# zxld400-9-leds-mk-2-driver.net
KiCad netlist of a schematic drawn in EAGLE
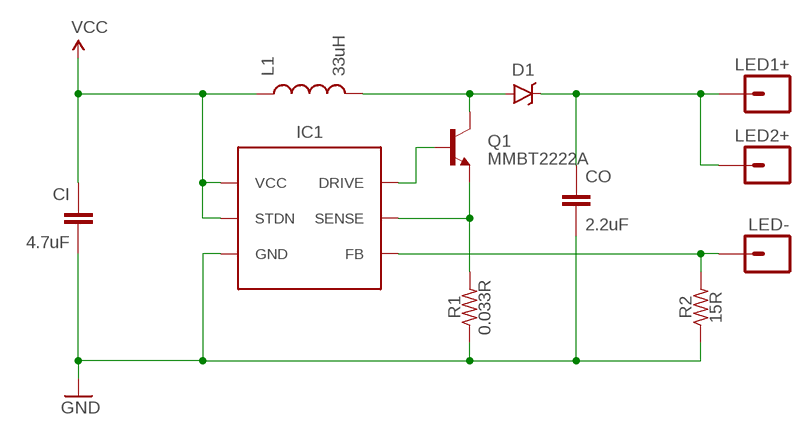
[diagram p0: schematic, sheet 1]

(export (version "E")
  (design (tool "Eeschema 10.0.6"))
  (components
    (comp (ref "CI")
      (value "4.7uF")
      (footprint "eagle-import:C0805")
      (libsource (lib "eagle-import") (part "CAPACITOR-CERAMICC0805"))
    )
    (comp (ref "CO")
      (value "2.2uF")
      (footprint "eagle-import:C0805")
      (libsource (lib "eagle-import") (part "CAPACITOR-CERAMICC0805"))
    )
    (comp (ref "D1")
      (value "DIODE-SCHOTTKYSMA")
      (footprint "eagle-import:SMA-DIODE-SCHOTTKY")
      (libsource (lib "eagle-import") (part "DIODE-SCHOTTKYSMA"))
    )
    (comp (ref "IC1")
      (value "ZXSC400")
      (footprint "eagle-import:SOT23-6")
      (libsource (lib "eagle-import") (part "ZXSC400"))
    )
    (comp (ref "L1")
      (value "33uH")
      (footprint "eagle-import:TAIYO-YUDEN-30XX")
      (libsource (lib "eagle-import") (part "INDUCTORTAIYO-YUDEN-30XX"))
    )
    (comp (ref "LED-")
      (value "M01PTH")
      (footprint "eagle-import:1X01")
      (libsource (lib "eagle-import") (part "M01PTH"))
    )
    (comp (ref "LED1+")
      (value "M01PTH")
      (footprint "eagle-import:1X01")
      (libsource (lib "eagle-import") (part "M01PTH"))
    )
    (comp (ref "LED2+")
      (value "M01PTH")
      (footprint "eagle-import:1X01")
      (libsource (lib "eagle-import") (part "M01PTH"))
    )
    (comp (ref "Q1")
      (value "MMBT2222A")
      (footprint "eagle-import:SOT23-3")
      (libsource (lib "eagle-import") (part "TRANSISTOR_NPNMMBT2222A"))
    )
    (comp (ref "R1")
      (value "0.033R")
      (footprint "eagle-import:R0805")
      (libsource (lib "eagle-import") (part "RESISTORR0805"))
    )
    (comp (ref "R2")
      (value "15R")
      (footprint "eagle-import:R0603")
      (libsource (lib "eagle-import") (part "RESISTORR0603"))
    )
  )
  (nets
    (net (code "1") (name "GND") (class "Default")
      (node (ref "CI") (pin "2") (pinfunction "2_2") (pintype "passive"))
      (node (ref "CO") (pin "2") (pinfunction "2_2") (pintype "passive"))
      (node (ref "IC1") (pin "2") (pinfunction "GND_2") (pintype "bidirectional"))
      (node (ref "R1") (pin "1") (pinfunction "1_1") (pintype "passive"))
      (node (ref "R2") (pin "1") (pinfunction "1_1") (pintype "passive"))
    )
    (net (code "2") (name "Net-(CO-Pad1)") (class "Default")
      (node (ref "CO") (pin "1") (pinfunction "1_1") (pintype "passive"))
      (node (ref "D1") (pin "C") (pinfunction "C_C") (pintype "passive"))
      (node (ref "LED1+") (pin "1") (pinfunction "1_1") (pintype "passive"))
      (node (ref "LED2+") (pin "1") (pinfunction "1_1") (pintype "passive"))
    )
    (net (code "3") (name "Net-(IC1-DRIVE)") (class "Default")
      (node (ref "IC1") (pin "6") (pinfunction "DRIVE_6") (pintype "bidirectional"))
      (node (ref "Q1") (pin "1") (pinfunction "B_1") (pintype "passive"))
    )
    (net (code "4") (name "Net-(IC1-FB)") (class "Default")
      (node (ref "IC1") (pin "5") (pinfunction "FB_5") (pintype "bidirectional"))
      (node (ref "LED-") (pin "1") (pinfunction "1_1") (pintype "passive"))
      (node (ref "R2") (pin "2") (pinfunction "2_2") (pintype "passive"))
    )
    (net (code "5") (name "Net-(IC1-SENSE)") (class "Default")
      (node (ref "IC1") (pin "4") (pinfunction "SENSE_4") (pintype "bidirectional"))
      (node (ref "Q1") (pin "2") (pinfunction "E_2") (pintype "passive"))
      (node (ref "R1") (pin "2") (pinfunction "2_2") (pintype "passive"))
    )
    (net (code "6") (name "Net-(Q1-C)") (class "Default")
      (node (ref "D1") (pin "A") (pinfunction "A_A") (pintype "passive"))
      (node (ref "L1") (pin "2") (pinfunction "2_2") (pintype "passive"))
      (node (ref "Q1") (pin "3") (pinfunction "C_3") (pintype "passive"))
    )
    (net (code "7") (name "VCC") (class "Default")
      (node (ref "CI") (pin "1") (pinfunction "1_1") (pintype "passive"))
      (node (ref "IC1") (pin "1") (pinfunction "VCC_1") (pintype "bidirectional"))
      (node (ref "IC1") (pin "3") (pinfunction "STDN_3") (pintype "bidirectional"))
      (node (ref "L1") (pin "1") (pinfunction "1_1") (pintype "passive"))
    )
  )
)
